# 10_-_Latching_Delay.net
KiCad netlist of a schematic drawn in Altium Designer
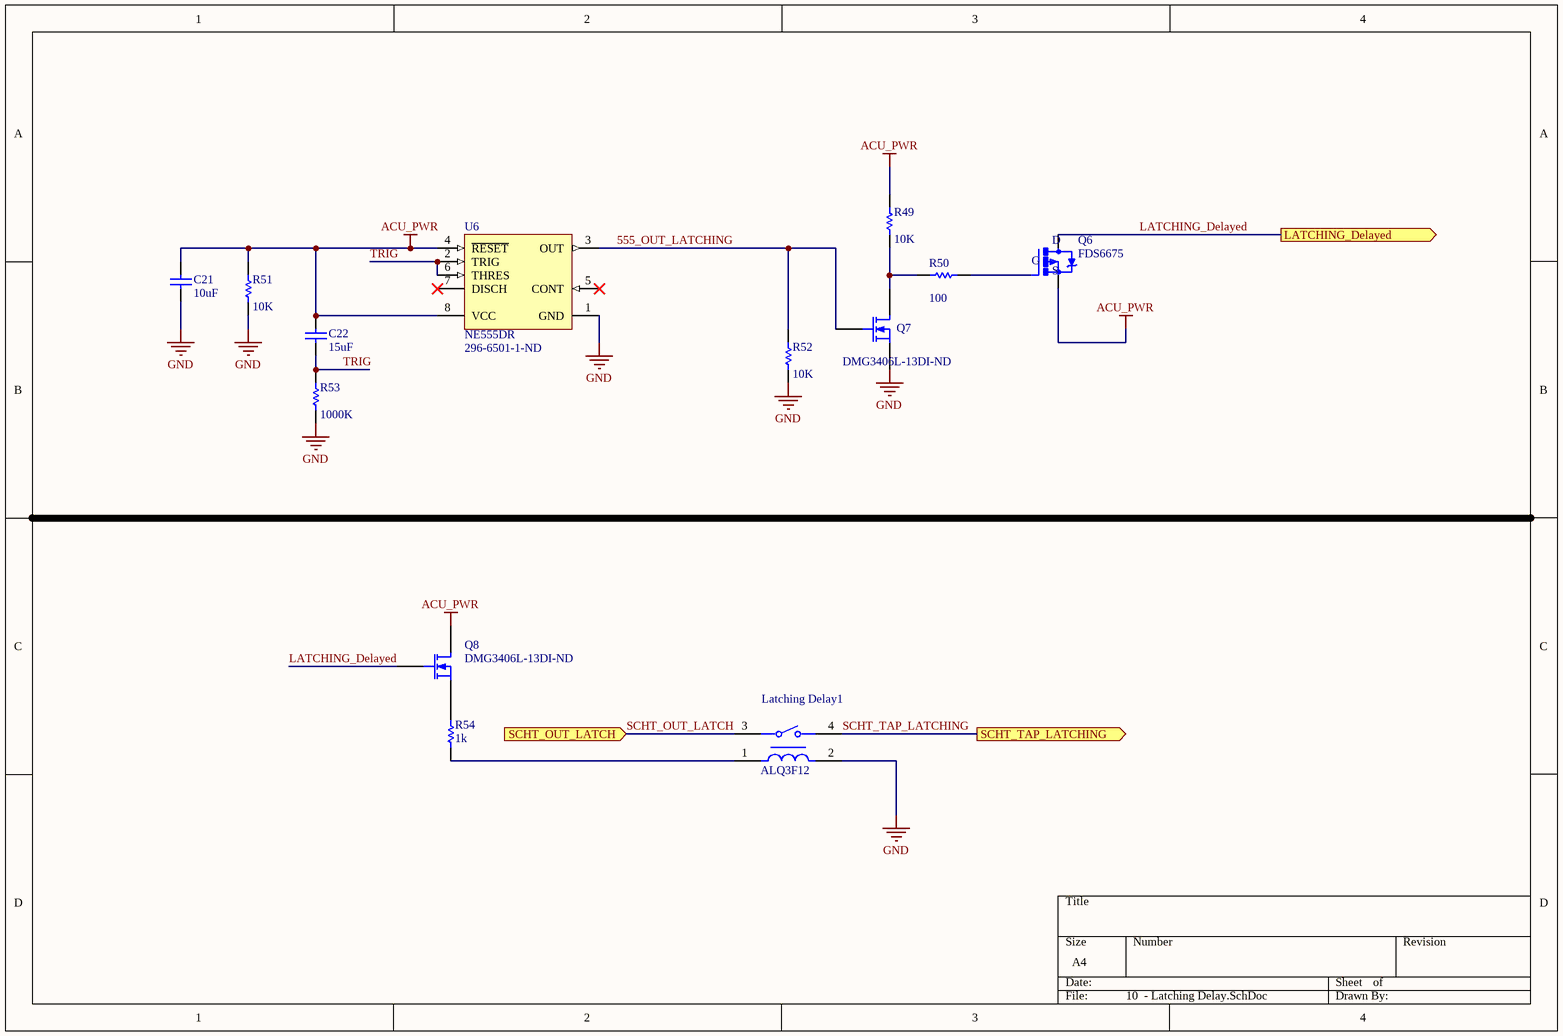
[diagram p0: 10  - Latching Delay.SchDoc]

(export (version "E")
  (design (tool "Eeschema 10.0.6"))
  (components
    (comp (ref "C21")
      (value "10uF")
      (footprint "1608[0603]")
      (description "Capacitor (Semiconductor SIM Model)")
      (fields (field (name "Comment") "Cap Semi") (field (name "PUBLISHER") "Altium Limited"))
      (libsource (lib "Miscellaneous Devices") (part "Cap Semi"))
    )
    (comp (ref "C22")
      (value "15uF")
      (footprint "1608[0603]")
      (description "Capacitor (Semiconductor SIM Model)")
      (fields (field (name "Comment") "Cap Semi") (field (name "PUBLISHER") "Altium Limited"))
      (libsource (lib "Miscellaneous Devices") (part "Cap Semi"))
    )
    (comp (ref "Latching Delay1")
      (value "ALQ3F12")
      (footprint "FP-ALQ3F12-MFG")
      (description "ALQ3F12 ALQ Series SPST 10 A 12 V PC Pin Through Hole Class F Insulation Power Relay")
      (libsource (lib "Altium Content Vault") (part "2840b51c2ee6fc134cbdaaad6983ecf"))
    )
    (comp (ref "Q6")
      (value "FDS6675")
      (footprint "SO08-E3")
      (description "P-Channel 30V 11A _Ta_ 2.5W _Ta_ Surface Mount 8-SOIC")
      (fields (field (name "MF") "ON Semiconductor"))
      (libsource (lib "SnapEDAsch") (part "FDS6675"))
    )
    (comp (ref "Q7")
      (value "~")
      (footprint "SOT-23_N")
      (description "N-Channel MOSFET")
      (fields
        (field (name "MANUFACTURER") "Infineon Technologies")
        (field (name "MANUFACTURER PART NUMBER") "IPD075N03L G")
        (field (name "SUPPLIER PART NUMBER 1") "DMG3406L-13DI-ND")
        (field (name "PUBLISHER") "Altium Limited")
      )
      (libsource (lib "Miscellaneous Devices") (part "MOSFET-N"))
    )
    (comp (ref "Q8")
      (value "~")
      (footprint "SOT-23_N")
      (description "N-Channel MOSFET")
      (fields
        (field (name "MANUFACTURER") "Infineon Technologies")
        (field (name "MANUFACTURER PART NUMBER") "IPD075N03L G")
        (field (name "SUPPLIER PART NUMBER 1") "DMG3406L-13DI-ND")
        (field (name "PUBLISHER") "Altium Limited")
      )
      (libsource (lib "Miscellaneous Devices") (part "MOSFET-N"))
    )
    (comp (ref "R49")
      (value "10K")
      (footprint "1608[0603]")
      (description "RES SMD 10K OHM 5% 1/4W 0603")
      (fields
        (field (name "MANUFACTURER") "Rohm Semiconductor")
        (field (name "MANUFACTURER PART NUMBER") "ESR03EZPJ103")
        (field (name "PUBLISHER") "Altium Limited")
      )
      (libsource (lib "Miscellaneous Devices") (part "Res1"))
    )
    (comp (ref "R50")
      (value "100")
      (footprint "1608[0603]")
      (description "RES SMD 100 OHM 5% 1/4W 0603")
      (fields
        (field (name "MANUFACTURER") "Rohm Semiconductor")
        (field (name "MANUFACTURER PART NUMBER") "ESR03EZPJ101")
        (field (name "PUBLISHER") "Altium Limited")
      )
      (libsource (lib "Miscellaneous Devices") (part "Res1"))
    )
    (comp (ref "R51")
      (value "10K")
      (footprint "1608[0603]")
      (description "RES SMD 10K OHM 5% 1/4W 0603")
      (fields
        (field (name "MANUFACTURER") "Rohm Semiconductor")
        (field (name "MANUFACTURER PART NUMBER") "ESR03EZPJ103")
        (field (name "PUBLISHER") "Altium Limited")
      )
      (libsource (lib "Miscellaneous Devices") (part "Res1"))
    )
    (comp (ref "R52")
      (value "10K")
      (footprint "1608[0603]")
      (description "RES SMD 10K OHM 5% 1/4W 0603")
      (fields
        (field (name "MANUFACTURER") "Rohm Semiconductor")
        (field (name "MANUFACTURER PART NUMBER") "ESR03EZPJ103")
        (field (name "PUBLISHER") "Altium Limited")
      )
      (libsource (lib "Miscellaneous Devices") (part "Res1"))
    )
    (comp (ref "R53")
      (value "1000K")
      (footprint "1608[0603]")
      (description "RES SMD 33K OHM 5% 1/4W 0603")
      (fields
        (field (name "MANUFACTURER") "Rohm Semiconductor")
        (field (name "MANUFACTURER PART NUMBER") "ESR03EZPJ333")
        (field (name "PUBLISHER") "Altium Limited")
      )
      (libsource (lib "Miscellaneous Devices") (part "Res1"))
    )
    (comp (ref "R54")
      (value "1k")
      (footprint "1608[0603]")
      (description "RES SMD 100 OHM 5% 1/4W 0603")
      (fields
        (field (name "MANUFACTURER") "Rohm Semiconductor")
        (field (name "MANUFACTURER PART NUMBER") "ESR03EZPJ101")
        (field (name "PUBLISHER") "Altium Limited")
      )
      (libsource (lib "Miscellaneous Devices") (part "Res1"))
    )
    (comp (ref "U6")
      (value "NE555DR")
      (footprint "D0008A_M")
      (fields (field (name "SUPPLIER PART NUMBER 1") "296-6501-1-ND"))
      (libsource (lib "Altium Content Vault") (part "CMP-1685-00007-1"))
    )
  )
  (nets
    (net (code "1") (name "/555_OUT_LATCHING") (class "Default")
      (node (ref "Q7") (pin "1") (pinfunction "G_1") (pintype "passive"))
      (node (ref "R52") (pin "2") (pinfunction "2_2") (pintype "passive"))
      (node (ref "U6") (pin "3") (pinfunction "OUT_3") (pintype "output"))
    )
    (net (code "2") (name "/LATCHING_Delayed") (class "Default")
      (node (ref "Q6") (pin "5-8") (pinfunction "D_5-8") (pintype "passive"))
      (node (ref "Q8") (pin "1") (pinfunction "G_1") (pintype "passive"))
    )
    (net (code "3") (name "/SCHT_OUT_LATCH") (class "Default")
      (node (ref "Latching Delay1") (pin "3") (pinfunction "3_3") (pintype "passive"))
    )
    (net (code "4") (name "/SCHT_TAP_LATCHING") (class "Default")
      (node (ref "Latching Delay1") (pin "4") (pinfunction "4_4") (pintype "passive"))
    )
    (net (code "5") (name "/TRIG") (class "Default")
      (node (ref "C22") (pin "1") (pinfunction "1_1") (pintype "passive"))
      (node (ref "R53") (pin "2") (pinfunction "2_2") (pintype "passive"))
      (node (ref "U6") (pin "2") (pinfunction "TRIG_2") (pintype "input"))
      (node (ref "U6") (pin "6") (pinfunction "THRES_6") (pintype "input"))
    )
    (net (code "6") (name "ACU_PWR") (class "Default")
      (node (ref "C21") (pin "2") (pinfunction "2_2") (pintype "passive"))
      (node (ref "C22") (pin "2") (pinfunction "2_2") (pintype "passive"))
      (node (ref "Q6") (pin "1-3") (pinfunction "S_1-3") (pintype "passive"))
      (node (ref "Q8") (pin "3") (pinfunction "D_3") (pintype "passive"))
      (node (ref "R49") (pin "2") (pinfunction "2_2") (pintype "passive"))
      (node (ref "R51") (pin "2") (pinfunction "2_2") (pintype "passive"))
      (node (ref "U6") (pin "4") (pinfunction "~{RESET}_4") (pintype "input"))
      (node (ref "U6") (pin "8") (pinfunction "VCC_8") (pintype "power_in"))
    )
    (net (code "7") (name "GND") (class "Default")
      (node (ref "C21") (pin "1") (pinfunction "1_1") (pintype "passive"))
      (node (ref "Latching Delay1") (pin "2") (pinfunction "2_2") (pintype "passive"))
      (node (ref "Q7") (pin "2") (pinfunction "S_2") (pintype "passive"))
      (node (ref "R51") (pin "1") (pinfunction "1_1") (pintype "passive"))
      (node (ref "R52") (pin "1") (pinfunction "1_1") (pintype "passive"))
      (node (ref "R53") (pin "1") (pinfunction "1_1") (pintype "passive"))
      (node (ref "U6") (pin "1") (pinfunction "GND_1") (pintype "power_in"))
    )
    (net (code "8") (name "Net-(Latching Delay1-Pad1)") (class "Default")
      (node (ref "Latching Delay1") (pin "1") (pinfunction "1_1") (pintype "passive"))
      (node (ref "R54") (pin "2") (pinfunction "2_2") (pintype "passive"))
    )
    (net (code "9") (name "Net-(Q6-G)") (class "Default")
      (node (ref "Q6") (pin "4") (pinfunction "G_4") (pintype "passive"))
      (node (ref "R50") (pin "2") (pinfunction "2_2") (pintype "passive"))
    )
    (net (code "10") (name "Net-(Q7-D)") (class "Default")
      (node (ref "Q7") (pin "3") (pinfunction "D_3") (pintype "passive"))
      (node (ref "R49") (pin "1") (pinfunction "1_1") (pintype "passive"))
      (node (ref "R50") (pin "1") (pinfunction "1_1") (pintype "passive"))
    )
    (net (code "11") (name "Net-(Q8-S)") (class "Default")
      (node (ref "Q8") (pin "2") (pinfunction "S_2") (pintype "passive"))
      (node (ref "R54") (pin "1") (pinfunction "1_1") (pintype "passive"))
    )
    (net (code "12") (name "unconnected-(U6-CONT-Pad5)") (class "Default")
      (node (ref "U6") (pin "5") (pinfunction "CONT_5") (pintype "input+no_connect"))
    )
    (net (code "13") (name "unconnected-(U6-DISCH-Pad7)") (class "Default")
      (node (ref "U6") (pin "7") (pinfunction "DISCH_7") (pintype "open_collector+no_connect"))
    )
  )
)
